# PL_Remote.net
KiCad netlist of a schematic drawn in Altium Designer
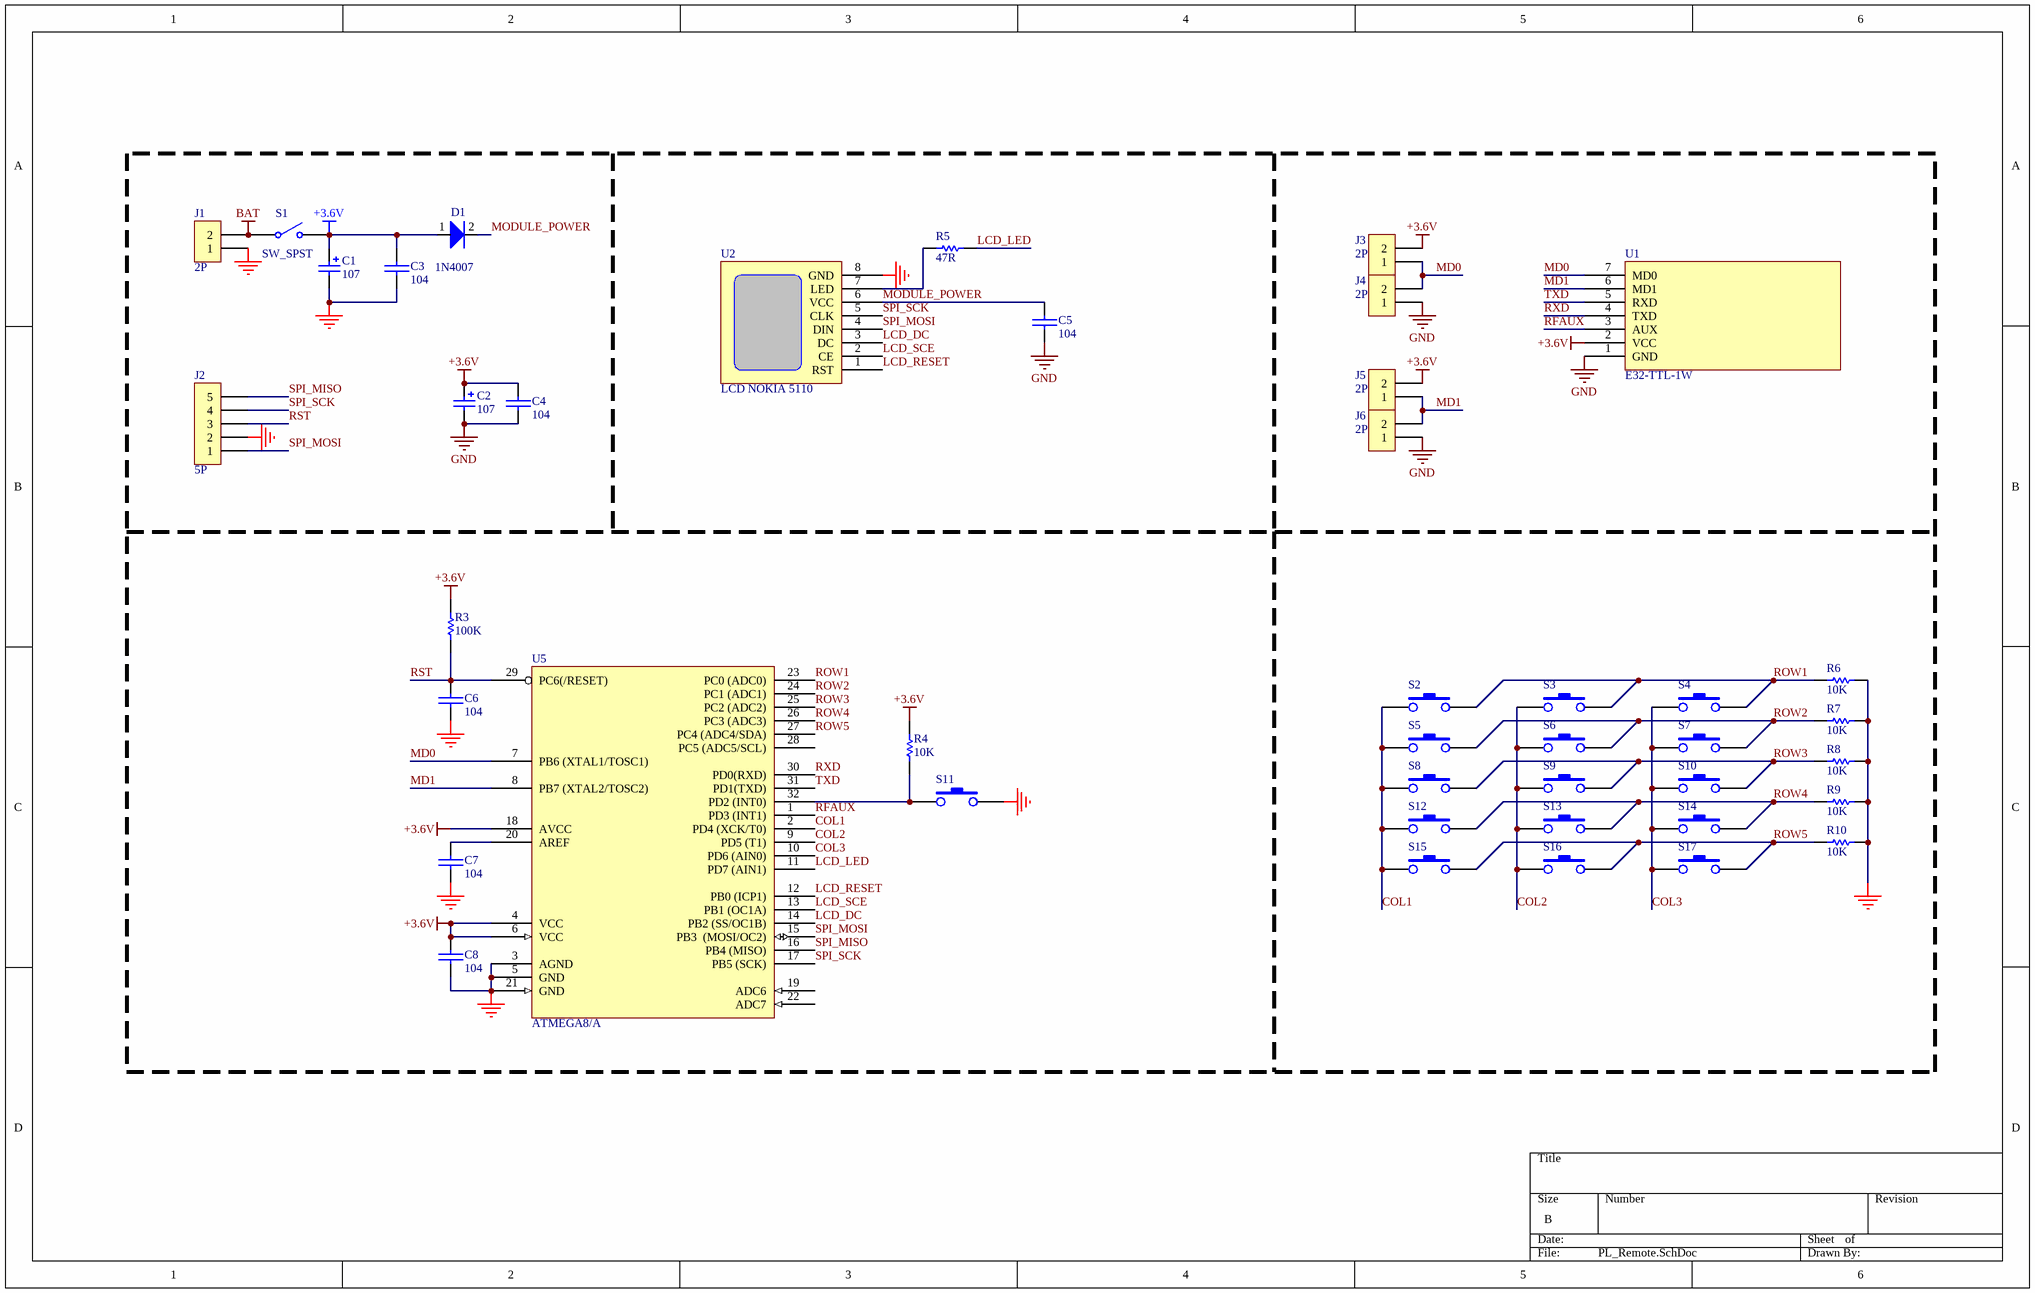
[diagram p0: PL_Remote.SchDoc]

(export (version "E")
  (design (tool "Eeschema 10.0.6"))
  (components
    (comp (ref "C1")
      (value "107")
      (footprint "SMC_D/WA")
      (description "Polarized Capacitor (Radial)")
      (fields (field (name "Comment") "Tụ hóa chân dán107") (field (name "PUBLISHER") "*"))
      (libsource (lib "DnsSchLib") (part "Cap Pol1"))
    )
    (comp (ref "C2")
      (value "107")
      (footprint "SMC_E/WA")
      (description "Polarized Capacitor (Radial)")
      (fields (field (name "Comment") "Tụ hóa chân dán107") (field (name "PUBLISHER") "*"))
      (libsource (lib "DnsSchLib") (part "Cap Pol1"))
    )
    (comp (ref "C3")
      (value "104")
      (footprint "0805C")
      (fields (field (name "Comment") "Tụ điện dán 0805104"))
      (libsource (lib "DnsSchLib") (part "CAP"))
    )
    (comp (ref "C4")
      (value "104")
      (footprint "0805C")
      (fields (field (name "Comment") "Tụ điện dán 0805104"))
      (libsource (lib "DnsSchLib") (part "CAP"))
    )
    (comp (ref "C5")
      (value "104")
      (footprint "0805C")
      (fields (field (name "Comment") "Tụ điện dán 0805104"))
      (libsource (lib "DnsSchLib") (part "CAP"))
    )
    (comp (ref "C6")
      (value "104")
      (footprint "0805C")
      (fields (field (name "Comment") "Tụ điện dán 0805104"))
      (libsource (lib "DnsSchLib") (part "CAP"))
    )
    (comp (ref "C7")
      (value "104")
      (footprint "0805C")
      (fields (field (name "Comment") "Tụ điện dán 0805104"))
      (libsource (lib "DnsSchLib") (part "CAP"))
    )
    (comp (ref "C8")
      (value "104")
      (footprint "0805C")
      (fields (field (name "Comment") "Tụ điện dán 0805104"))
      (libsource (lib "DnsSchLib") (part "CAP"))
    )
    (comp (ref "D1")
      (value "Diode chân dán 1A1N4007")
      (footprint "SMC_D/WA")
      (fields (field (name "VALUE2") "1N4007"))
      (libsource (lib "DnsSchLib") (part "DIODE"))
    )
    (comp (ref "J1")
      (value "2P")
      (footprint "HDR1x2")
      (fields (field (name "Comment") "Jump đực loại thẳng, 2.54mm2P"))
      (libsource (lib "DnsSchLib") (part "CON2"))
    )
    (comp (ref "J2")
      (value "5P")
      (footprint "HDR1x5")
      (description "Connector")
      (fields (field (name "Comment") "Jump đực chân thẳng, 2.54mm 5P"))
      (libsource (lib "*") (part "CON5"))
    )
    (comp (ref "J3")
      (value "2P")
      (footprint "XPAD")
      (fields (field (name "Comment") "Jumper2P"))
      (libsource (lib "DnsSchLib") (part "CON2"))
    )
    (comp (ref "J4")
      (value "2P")
      (footprint "XPAD")
      (fields (field (name "Comment") "Jumper2P"))
      (libsource (lib "DnsSchLib") (part "CON2"))
    )
    (comp (ref "J5")
      (value "2P")
      (footprint "XPAD")
      (fields (field (name "Comment") "Jumper2P"))
      (libsource (lib "DnsSchLib") (part "CON2"))
    )
    (comp (ref "J6")
      (value "2P")
      (footprint "XPAD")
      (fields (field (name "Comment") "Jumper2P"))
      (libsource (lib "DnsSchLib") (part "CON2"))
    )
    (comp (ref "R3")
      (value "100K")
      (footprint "0805DD")
      (description "Semiconductor Resistor")
      (fields (field (name "Comment") "Điện trở dán 0805100K") (field (name "PUBLISHER") "*"))
      (libsource (lib "DnsSchLib") (part "Res Semi"))
    )
    (comp (ref "R4")
      (value "10K")
      (footprint "0805DD")
      (description "Semiconductor Resistor")
      (fields (field (name "Comment") "Điện trở dán 080510K") (field (name "PUBLISHER") "*"))
      (libsource (lib "DnsSchLib") (part "Res Semi"))
    )
    (comp (ref "R5")
      (value "47R")
      (footprint "0805DD")
      (description "Semiconductor Resistor")
      (fields (field (name "Comment") "Điện trở dán 080547R") (field (name "PUBLISHER") "*"))
      (libsource (lib "DnsSchLib") (part "Res Semi"))
    )
    (comp (ref "R6")
      (value "10K")
      (footprint "0805DD")
      (description "Semiconductor Resistor")
      (fields (field (name "Comment") "Điện trở dán 080510K") (field (name "PUBLISHER") "*"))
      (libsource (lib "DnsSchLib") (part "Res Semi"))
    )
    (comp (ref "R7")
      (value "10K")
      (footprint "0805DD")
      (description "Semiconductor Resistor")
      (fields (field (name "Comment") "Điện trở dán 080510K") (field (name "PUBLISHER") "*"))
      (libsource (lib "DnsSchLib") (part "Res Semi"))
    )
    (comp (ref "R8")
      (value "10K")
      (footprint "0805DD")
      (description "Semiconductor Resistor")
      (fields (field (name "Comment") "Điện trở dán 080510K") (field (name "PUBLISHER") "*"))
      (libsource (lib "DnsSchLib") (part "Res Semi"))
    )
    (comp (ref "R9")
      (value "10K")
      (footprint "0805DD")
      (description "Semiconductor Resistor")
      (fields (field (name "Comment") "Điện trở dán 080510K") (field (name "PUBLISHER") "*"))
      (libsource (lib "DnsSchLib") (part "Res Semi"))
    )
    (comp (ref "R10")
      (value "10K")
      (footprint "0805DD")
      (description "Semiconductor Resistor")
      (fields (field (name "Comment") "Điện trở dán 080510K") (field (name "PUBLISHER") "*"))
      (libsource (lib "DnsSchLib") (part "Res Semi"))
    )
    (comp (ref "S1")
      (value "SW_SPST")
      (footprint "SPST-2")
      (description "Single-Pole, Single-Throw Switch")
      (fields (field (name "Comment") "Công tắc chân cắm BIT X1") (field (name "PUBLISHER") "Altium Limited"))
      (libsource (lib "Miscellaneous Devices") (part "SW-SPST"))
    )
    (comp (ref "S2")
      (value "Công tắc chip chân cắm, 4 chân6x6x4mm")
      (footprint "CHIP")
      (libsource (lib "DnsSchLib") (part "SW-PB"))
    )
    (comp (ref "S3")
      (value "Công tắc chip chân cắm, 4 chân6x6x4mm")
      (footprint "CHIP")
      (libsource (lib "DnsSchLib") (part "SW-PB"))
    )
    (comp (ref "S4")
      (value "Công tắc chip chân cắm, 4 chân6x6x4mm")
      (footprint "CHIP")
      (libsource (lib "DnsSchLib") (part "SW-PB"))
    )
    (comp (ref "S5")
      (value "Công tắc chip chân cắm, 4 chân6x6x4mm")
      (footprint "CHIP")
      (libsource (lib "DnsSchLib") (part "SW-PB"))
    )
    (comp (ref "S6")
      (value "Công tắc chip chân cắm, 4 chân6x6x4mm")
      (footprint "CHIP")
      (libsource (lib "DnsSchLib") (part "SW-PB"))
    )
    (comp (ref "S7")
      (value "Công tắc chip chân cắm, 4 chân6x6x4mm")
      (footprint "CHIP")
      (libsource (lib "DnsSchLib") (part "SW-PB"))
    )
    (comp (ref "S8")
      (value "Công tắc chip chân cắm, 4 chân6x6x4mm")
      (footprint "CHIP")
      (libsource (lib "DnsSchLib") (part "SW-PB"))
    )
    (comp (ref "S9")
      (value "Công tắc chip chân cắm, 4 chân6x6x4mm")
      (footprint "CHIP")
      (libsource (lib "DnsSchLib") (part "SW-PB"))
    )
    (comp (ref "S10")
      (value "Công tắc chip chân cắm, 4 chân6x6x4mm")
      (footprint "CHIP")
      (libsource (lib "DnsSchLib") (part "SW-PB"))
    )
    (comp (ref "S11")
      (value "Công tắc chip chân cắm, 4 chân6x6x4mm")
      (footprint "CHIP")
      (libsource (lib "DnsSchLib") (part "SW-PB"))
    )
    (comp (ref "S12")
      (value "Công tắc chip chân cắm, 4 chân6x6x4mm")
      (footprint "CHIP")
      (libsource (lib "DnsSchLib") (part "SW-PB"))
    )
    (comp (ref "S13")
      (value "Công tắc chip chân cắm, 4 chân6x6x4mm")
      (footprint "CHIP")
      (libsource (lib "DnsSchLib") (part "SW-PB"))
    )
    (comp (ref "S14")
      (value "Công tắc chip chân cắm, 4 chân6x6x4mm")
      (footprint "CHIP")
      (libsource (lib "DnsSchLib") (part "SW-PB"))
    )
    (comp (ref "S15")
      (value "Công tắc chip chân cắm, 4 chân6x6x4mm")
      (footprint "CHIP")
      (libsource (lib "DnsSchLib") (part "SW-PB"))
    )
    (comp (ref "S16")
      (value "Công tắc chip chân cắm, 4 chân6x6x4mm")
      (footprint "CHIP")
      (libsource (lib "DnsSchLib") (part "SW-PB"))
    )
    (comp (ref "S17")
      (value "Công tắc chip chân cắm, 4 chân6x6x4mm")
      (footprint "CHIP")
      (libsource (lib "DnsSchLib") (part "SW-PB"))
    )
    (comp (ref "U1")
      (value "E32-TTL-1W")
      (footprint "RF_AS32")
      (description "AS32-TTL-1W")
      (fields (field (name "Comment") "Module thu phát không dây RFE32-TTL-1W"))
      (libsource (lib "DnsSchLib") (part "AS32-TTL-1W"))
    )
    (comp (ref "U2")
      (value "LCD NOKIA 5110")
      (footprint "NOKIA5110T")
      (libsource (lib "DnsSchLib") (part "LCD NOKIA 5110"))
    )
    (comp (ref "U5")
      (value "ATMEGA8/A")
      (footprint "ATMEGA8")
      (description "TQFP package")
      (fields (field (name "Comment") "Vi điều khiển ATMEL chân dánATMEGA8/A"))
      (libsource (lib "DnsSchLib") (part "ATMEGA8-A"))
    )
  )
  (nets
    (net (code "1") (name "+3.6V") (class "Default")
      (node (ref "C1") (pin "1") (pinfunction "1_1") (pintype "passive"))
      (node (ref "C2") (pin "1") (pinfunction "1_1") (pintype "passive"))
      (node (ref "C3") (pin "1") (pinfunction "1_1") (pintype "passive"))
      (node (ref "C4") (pin "2") (pinfunction "2_2") (pintype "passive"))
      (node (ref "C8") (pin "1") (pinfunction "1_1") (pintype "passive"))
      (node (ref "D1") (pin "1") (pinfunction "A_1") (pintype "passive"))
      (node (ref "J3") (pin "2") (pinfunction "2_2") (pintype "passive"))
      (node (ref "J5") (pin "2") (pinfunction "2_2") (pintype "passive"))
      (node (ref "R3") (pin "2") (pinfunction "2_2") (pintype "passive"))
      (node (ref "R4") (pin "2") (pinfunction "2_2") (pintype "passive"))
      (node (ref "S1") (pin "2") (pinfunction "NO_2") (pintype "passive"))
      (node (ref "U1") (pin "2") (pinfunction "VCC_2") (pintype "passive"))
      (node (ref "U5") (pin "18") (pinfunction "AVCC_18") (pintype "passive"))
      (node (ref "U5") (pin "4") (pinfunction "VCC_4") (pintype "passive"))
      (node (ref "U5") (pin "6") (pinfunction "VCC_6") (pintype "input"))
    )
    (net (code "2") (name "/COL1") (class "Default")
      (node (ref "S12") (pin "1") (pinfunction "1_1") (pintype "passive"))
      (node (ref "S15") (pin "1") (pinfunction "1_1") (pintype "passive"))
      (node (ref "S2") (pin "1") (pinfunction "1_1") (pintype "passive"))
      (node (ref "S5") (pin "1") (pinfunction "1_1") (pintype "passive"))
      (node (ref "S8") (pin "1") (pinfunction "1_1") (pintype "passive"))
      (node (ref "U5") (pin "2") (pinfunction "PD4_(XCK/T0)_2") (pintype "passive"))
    )
    (net (code "3") (name "/COL2") (class "Default")
      (node (ref "S13") (pin "1") (pinfunction "1_1") (pintype "passive"))
      (node (ref "S16") (pin "1") (pinfunction "1_1") (pintype "passive"))
      (node (ref "S3") (pin "1") (pinfunction "1_1") (pintype "passive"))
      (node (ref "S6") (pin "1") (pinfunction "1_1") (pintype "passive"))
      (node (ref "S9") (pin "1") (pinfunction "1_1") (pintype "passive"))
      (node (ref "U5") (pin "9") (pinfunction "PD5_(T1)_9") (pintype "passive"))
    )
    (net (code "4") (name "/COL3") (class "Default")
      (node (ref "S10") (pin "1") (pinfunction "1_1") (pintype "passive"))
      (node (ref "S14") (pin "1") (pinfunction "1_1") (pintype "passive"))
      (node (ref "S17") (pin "1") (pinfunction "1_1") (pintype "passive"))
      (node (ref "S4") (pin "1") (pinfunction "1_1") (pintype "passive"))
      (node (ref "S7") (pin "1") (pinfunction "1_1") (pintype "passive"))
      (node (ref "U5") (pin "10") (pinfunction "PD6_(AIN0)_10") (pintype "passive"))
    )
    (net (code "5") (name "/LCD_DC") (class "Default")
      (node (ref "U2") (pin "3") (pinfunction "DC_3") (pintype "passive"))
      (node (ref "U5") (pin "14") (pinfunction "PB2_(SS/OC1B)_14") (pintype "passive"))
    )
    (net (code "6") (name "/LCD_LED") (class "Default")
      (node (ref "R5") (pin "2") (pinfunction "2_2") (pintype "passive"))
      (node (ref "U5") (pin "11") (pinfunction "PD7_(AIN1)_11") (pintype "passive"))
    )
    (net (code "7") (name "/LCD_RESET") (class "Default")
      (node (ref "U2") (pin "1") (pinfunction "RST_1") (pintype "passive"))
      (node (ref "U5") (pin "12") (pinfunction "PB0_(ICP1)_12") (pintype "passive"))
    )
    (net (code "8") (name "/LCD_SCE") (class "Default")
      (node (ref "U2") (pin "2") (pinfunction "CE_2") (pintype "passive"))
      (node (ref "U5") (pin "13") (pinfunction "PB1_(OC1A)_13") (pintype "passive"))
    )
    (net (code "9") (name "/MD0") (class "Default")
      (node (ref "J3") (pin "1") (pinfunction "1_1") (pintype "passive"))
      (node (ref "J4") (pin "2") (pinfunction "2_2") (pintype "passive"))
      (node (ref "U1") (pin "7") (pinfunction "MD0_7") (pintype "passive"))
      (node (ref "U5") (pin "7") (pinfunction "PB6_(XTAL1/TOSC1)_7") (pintype "passive"))
    )
    (net (code "10") (name "/MD1") (class "Default")
      (node (ref "J5") (pin "1") (pinfunction "1_1") (pintype "passive"))
      (node (ref "J6") (pin "2") (pinfunction "2_2") (pintype "passive"))
      (node (ref "U1") (pin "6") (pinfunction "MD1_6") (pintype "passive"))
      (node (ref "U5") (pin "8") (pinfunction "PB7_(XTAL2/TOSC2)_8") (pintype "passive"))
    )
    (net (code "11") (name "/MODULE_POWER") (class "Default")
      (node (ref "C5") (pin "1") (pinfunction "1_1") (pintype "passive"))
      (node (ref "D1") (pin "2") (pinfunction "K_2") (pintype "passive"))
      (node (ref "U2") (pin "6") (pinfunction "VCC_6") (pintype "passive"))
    )
    (net (code "12") (name "/RFAUX") (class "Default")
      (node (ref "U1") (pin "3") (pinfunction "AUX_3") (pintype "passive"))
      (node (ref "U5") (pin "1") (pinfunction "PD3_(INT1)_1") (pintype "passive"))
    )
    (net (code "13") (name "/ROW1") (class "Default")
      (node (ref "R6") (pin "1") (pinfunction "1_1") (pintype "passive"))
      (node (ref "S2") (pin "2") (pinfunction "2_2") (pintype "passive"))
      (node (ref "S3") (pin "2") (pinfunction "2_2") (pintype "passive"))
      (node (ref "S4") (pin "2") (pinfunction "2_2") (pintype "passive"))
      (node (ref "U5") (pin "23") (pinfunction "PC0_(ADC0)_23") (pintype "passive"))
    )
    (net (code "14") (name "/ROW2") (class "Default")
      (node (ref "R7") (pin "1") (pinfunction "1_1") (pintype "passive"))
      (node (ref "S5") (pin "2") (pinfunction "2_2") (pintype "passive"))
      (node (ref "S6") (pin "2") (pinfunction "2_2") (pintype "passive"))
      (node (ref "S7") (pin "2") (pinfunction "2_2") (pintype "passive"))
      (node (ref "U5") (pin "24") (pinfunction "PC1_(ADC1)_24") (pintype "passive"))
    )
    (net (code "15") (name "/ROW3") (class "Default")
      (node (ref "R8") (pin "1") (pinfunction "1_1") (pintype "passive"))
      (node (ref "S10") (pin "2") (pinfunction "2_2") (pintype "passive"))
      (node (ref "S8") (pin "2") (pinfunction "2_2") (pintype "passive"))
      (node (ref "S9") (pin "2") (pinfunction "2_2") (pintype "passive"))
      (node (ref "U5") (pin "25") (pinfunction "PC2_(ADC2)_25") (pintype "passive"))
    )
    (net (code "16") (name "/ROW4") (class "Default")
      (node (ref "R9") (pin "1") (pinfunction "1_1") (pintype "passive"))
      (node (ref "S12") (pin "2") (pinfunction "2_2") (pintype "passive"))
      (node (ref "S13") (pin "2") (pinfunction "2_2") (pintype "passive"))
      (node (ref "S14") (pin "2") (pinfunction "2_2") (pintype "passive"))
      (node (ref "U5") (pin "26") (pinfunction "PC3_(ADC3)_26") (pintype "passive"))
    )
    (net (code "17") (name "/ROW5") (class "Default")
      (node (ref "R10") (pin "1") (pinfunction "1_1") (pintype "passive"))
      (node (ref "S15") (pin "2") (pinfunction "2_2") (pintype "passive"))
      (node (ref "S16") (pin "2") (pinfunction "2_2") (pintype "passive"))
      (node (ref "S17") (pin "2") (pinfunction "2_2") (pintype "passive"))
      (node (ref "U5") (pin "27") (pinfunction "PC4_(ADC4/SDA)_27") (pintype "passive"))
    )
    (net (code "18") (name "/RST") (class "Default")
      (node (ref "C6") (pin "1") (pinfunction "1_1") (pintype "passive"))
      (node (ref "J2") (pin "3") (pinfunction "3_3") (pintype "passive"))
      (node (ref "R3") (pin "1") (pinfunction "1_1") (pintype "passive"))
      (node (ref "U5") (pin "29") (pinfunction "PC6(/RESET)_29") (pintype "passive"))
    )
    (net (code "19") (name "/RXD") (class "Default")
      (node (ref "U1") (pin "4") (pinfunction "TXD_4") (pintype "passive"))
      (node (ref "U5") (pin "30") (pinfunction "PD0(RXD)_30") (pintype "passive"))
    )
    (net (code "20") (name "/SPI_MISO") (class "Default")
      (node (ref "J2") (pin "5") (pinfunction "5_5") (pintype "passive"))
      (node (ref "U5") (pin "16") (pinfunction "PB4_(MISO)_16") (pintype "passive"))
    )
    (net (code "21") (name "/SPI_MOSI") (class "Default")
      (node (ref "J2") (pin "1") (pinfunction "1_1") (pintype "passive"))
      (node (ref "U2") (pin "4") (pinfunction "DIN_4") (pintype "passive"))
      (node (ref "U5") (pin "15") (pinfunction "PB3__(MOSI/OC2)_15") (pintype "bidirectional"))
    )
    (net (code "22") (name "/SPI_SCK") (class "Default")
      (node (ref "J2") (pin "4") (pinfunction "4_4") (pintype "passive"))
      (node (ref "U2") (pin "5") (pinfunction "CLK_5") (pintype "passive"))
      (node (ref "U5") (pin "17") (pinfunction "PB5_(SCK)_17") (pintype "passive"))
    )
    (net (code "23") (name "/TXD") (class "Default")
      (node (ref "U1") (pin "5") (pinfunction "RXD_5") (pintype "passive"))
      (node (ref "U5") (pin "31") (pinfunction "PD1(TXD)_31") (pintype "passive"))
    )
    (net (code "24") (name "BAT") (class "Default")
      (node (ref "J1") (pin "2") (pinfunction "2_2") (pintype "passive"))
      (node (ref "S1") (pin "1") (pinfunction "COMMON_1") (pintype "passive"))
    )
    (net (code "25") (name "GND") (class "Default")
      (node (ref "C1") (pin "2") (pinfunction "2_2") (pintype "passive"))
      (node (ref "C2") (pin "2") (pinfunction "2_2") (pintype "passive"))
      (node (ref "C3") (pin "2") (pinfunction "2_2") (pintype "passive"))
      (node (ref "C4") (pin "1") (pinfunction "1_1") (pintype "passive"))
      (node (ref "C5") (pin "2") (pinfunction "2_2") (pintype "passive"))
      (node (ref "C6") (pin "2") (pinfunction "2_2") (pintype "passive"))
      (node (ref "C7") (pin "2") (pinfunction "2_2") (pintype "passive"))
      (node (ref "C8") (pin "2") (pinfunction "2_2") (pintype "passive"))
      (node (ref "J1") (pin "1") (pinfunction "1_1") (pintype "passive"))
      (node (ref "J2") (pin "2") (pinfunction "2_2") (pintype "passive"))
      (node (ref "J4") (pin "1") (pinfunction "1_1") (pintype "passive"))
      (node (ref "J6") (pin "1") (pinfunction "1_1") (pintype "passive"))
      (node (ref "R10") (pin "2") (pinfunction "2_2") (pintype "passive"))
      (node (ref "R6") (pin "2") (pinfunction "2_2") (pintype "passive"))
      (node (ref "R7") (pin "2") (pinfunction "2_2") (pintype "passive"))
      (node (ref "R8") (pin "2") (pinfunction "2_2") (pintype "passive"))
      (node (ref "R9") (pin "2") (pinfunction "2_2") (pintype "passive"))
      (node (ref "S11") (pin "2") (pinfunction "2_2") (pintype "passive"))
      (node (ref "U1") (pin "1") (pinfunction "GND_1") (pintype "passive"))
      (node (ref "U2") (pin "8") (pinfunction "GND_8") (pintype "passive"))
      (node (ref "U5") (pin "21") (pinfunction "GND_21") (pintype "input"))
      (node (ref "U5") (pin "3") (pinfunction "AGND_3") (pintype "passive"))
      (node (ref "U5") (pin "5") (pinfunction "GND_5") (pintype "passive"))
    )
    (net (code "26") (name "Net-(U2-LED)") (class "Default")
      (node (ref "R5") (pin "1") (pinfunction "1_1") (pintype "passive"))
      (node (ref "U2") (pin "7") (pinfunction "LED_7") (pintype "passive"))
    )
    (net (code "27") (name "Net-(U5-AREF)") (class "Default")
      (node (ref "C7") (pin "1") (pinfunction "1_1") (pintype "passive"))
      (node (ref "U5") (pin "20") (pinfunction "AREF_20") (pintype "passive"))
    )
    (net (code "28") (name "Net-(U5-PD2_(INT0))") (class "Default")
      (node (ref "R4") (pin "1") (pinfunction "1_1") (pintype "passive"))
      (node (ref "S11") (pin "1") (pinfunction "1_1") (pintype "passive"))
      (node (ref "U5") (pin "32") (pinfunction "PD2_(INT0)_32") (pintype "passive"))
    )
    (net (code "29") (name "unconnected-(U5-ADC6-Pad19)") (class "Default")
      (node (ref "U5") (pin "19") (pinfunction "ADC6_19") (pintype "input"))
    )
    (net (code "30") (name "unconnected-(U5-ADC7-Pad22)") (class "Default")
      (node (ref "U5") (pin "22") (pinfunction "ADC7_22") (pintype "input"))
    )
    (net (code "31") (name "unconnected-(U5-PC5_(ADC5{slash}SCL)-Pad28)") (class "Default")
      (node (ref "U5") (pin "28") (pinfunction "PC5_(ADC5/SCL)_28") (pintype "passive"))
    )
  )
)
